# FiveToggleBreakout.net
KiCad netlist of a schematic drawn in EAGLE
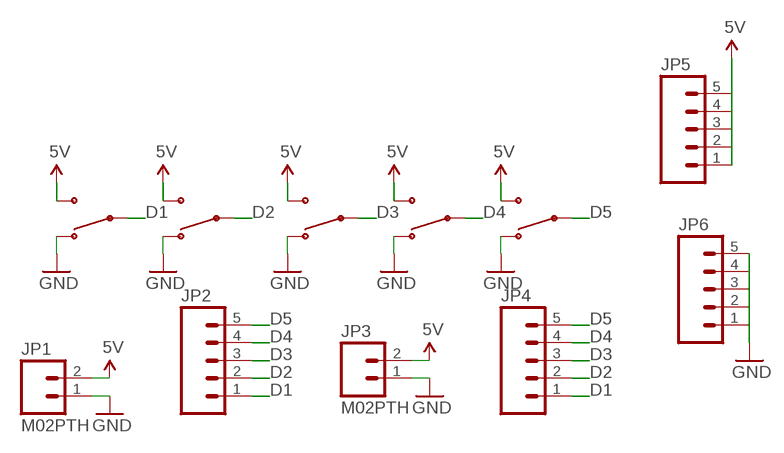
[diagram p0: schematic, sheet 1]

(export (version "E")
  (design (tool "Eeschema 10.0.6"))
  (components
    (comp (ref "JP1")
      (value "M02PTH")
      (footprint "eagle-import:1X02")
      (libsource (lib "eagle-import") (part "M02PTH"))
    )
    (comp (ref "JP2")
      (value "M05PTH")
      (footprint "eagle-import:1X05")
      (libsource (lib "eagle-import") (part "M05PTH"))
    )
    (comp (ref "JP3")
      (value "M02PTH")
      (footprint "eagle-import:1X02")
      (libsource (lib "eagle-import") (part "M02PTH"))
    )
    (comp (ref "JP4")
      (value "M05PTH")
      (footprint "eagle-import:1X05")
      (libsource (lib "eagle-import") (part "M05PTH"))
    )
    (comp (ref "JP5")
      (value "M05PTH")
      (footprint "eagle-import:1X05")
      (libsource (lib "eagle-import") (part "M05PTH"))
    )
    (comp (ref "JP6")
      (value "M05PTH")
      (footprint "eagle-import:1X05")
      (libsource (lib "eagle-import") (part "M05PTH"))
    )
    (comp (ref "U$1")
      (value "SPDTSPDT")
      (footprint "eagle-import:TOGGLE_SPDT")
      (libsource (lib "eagle-import") (part "SPDTSPDT"))
    )
    (comp (ref "U$2")
      (value "SPDTSPDT")
      (footprint "eagle-import:TOGGLE_SPDT")
      (libsource (lib "eagle-import") (part "SPDTSPDT"))
    )
    (comp (ref "U$3")
      (value "SPDTSPDT")
      (footprint "eagle-import:TOGGLE_SPDT")
      (libsource (lib "eagle-import") (part "SPDTSPDT"))
    )
    (comp (ref "U$4")
      (value "SPDTSPDT")
      (footprint "eagle-import:TOGGLE_SPDT")
      (libsource (lib "eagle-import") (part "SPDTSPDT"))
    )
    (comp (ref "U$5")
      (value "SPDTSPDT")
      (footprint "eagle-import:TOGGLE_SPDT")
      (libsource (lib "eagle-import") (part "SPDTSPDT"))
    )
  )
  (nets
    (net (code "1") (name "/D1") (class "Default")
      (node (ref "JP2") (pin "1") (pinfunction "1_1") (pintype "passive"))
      (node (ref "JP4") (pin "1") (pinfunction "1_1") (pintype "passive"))
      (node (ref "U$1") (pin "2") (pinfunction "2_2") (pintype "bidirectional"))
    )
    (net (code "2") (name "/D2") (class "Default")
      (node (ref "JP2") (pin "2") (pinfunction "2_2") (pintype "passive"))
      (node (ref "JP4") (pin "2") (pinfunction "2_2") (pintype "passive"))
      (node (ref "U$2") (pin "2") (pinfunction "2_2") (pintype "bidirectional"))
    )
    (net (code "3") (name "/D3") (class "Default")
      (node (ref "JP2") (pin "3") (pinfunction "3_3") (pintype "passive"))
      (node (ref "JP4") (pin "3") (pinfunction "3_3") (pintype "passive"))
      (node (ref "U$3") (pin "2") (pinfunction "2_2") (pintype "bidirectional"))
    )
    (net (code "4") (name "/D4") (class "Default")
      (node (ref "JP2") (pin "4") (pinfunction "4_4") (pintype "passive"))
      (node (ref "JP4") (pin "4") (pinfunction "4_4") (pintype "passive"))
      (node (ref "U$4") (pin "2") (pinfunction "2_2") (pintype "bidirectional"))
    )
    (net (code "5") (name "/D5") (class "Default")
      (node (ref "JP2") (pin "5") (pinfunction "5_5") (pintype "passive"))
      (node (ref "JP4") (pin "5") (pinfunction "5_5") (pintype "passive"))
      (node (ref "U$5") (pin "2") (pinfunction "2_2") (pintype "bidirectional"))
    )
    (net (code "6") (name "5V") (class "Default")
      (node (ref "JP1") (pin "2") (pinfunction "2_2") (pintype "passive"))
      (node (ref "JP3") (pin "2") (pinfunction "2_2") (pintype "passive"))
      (node (ref "JP5") (pin "1") (pinfunction "1_1") (pintype "passive"))
      (node (ref "JP5") (pin "2") (pinfunction "2_2") (pintype "passive"))
      (node (ref "JP5") (pin "3") (pinfunction "3_3") (pintype "passive"))
      (node (ref "JP5") (pin "4") (pinfunction "4_4") (pintype "passive"))
      (node (ref "JP5") (pin "5") (pinfunction "5_5") (pintype "passive"))
      (node (ref "U$1") (pin "3") (pinfunction "3_3") (pintype "bidirectional"))
      (node (ref "U$2") (pin "3") (pinfunction "3_3") (pintype "bidirectional"))
      (node (ref "U$3") (pin "3") (pinfunction "3_3") (pintype "bidirectional"))
      (node (ref "U$4") (pin "3") (pinfunction "3_3") (pintype "bidirectional"))
      (node (ref "U$5") (pin "3") (pinfunction "3_3") (pintype "bidirectional"))
    )
    (net (code "7") (name "GND") (class "Default")
      (node (ref "JP1") (pin "1") (pinfunction "1_1") (pintype "passive"))
      (node (ref "JP3") (pin "1") (pinfunction "1_1") (pintype "passive"))
      (node (ref "JP6") (pin "1") (pinfunction "1_1") (pintype "passive"))
      (node (ref "JP6") (pin "2") (pinfunction "2_2") (pintype "passive"))
      (node (ref "JP6") (pin "3") (pinfunction "3_3") (pintype "passive"))
      (node (ref "JP6") (pin "4") (pinfunction "4_4") (pintype "passive"))
      (node (ref "JP6") (pin "5") (pinfunction "5_5") (pintype "passive"))
      (node (ref "U$1") (pin "1") (pinfunction "1_1") (pintype "bidirectional"))
      (node (ref "U$2") (pin "1") (pinfunction "1_1") (pintype "bidirectional"))
      (node (ref "U$3") (pin "1") (pinfunction "1_1") (pintype "bidirectional"))
      (node (ref "U$4") (pin "1") (pinfunction "1_1") (pintype "bidirectional"))
      (node (ref "U$5") (pin "1") (pinfunction "1_1") (pintype "bidirectional"))
    )
  )
)
